# E8-C.net
KiCad netlist of a schematic drawn in EAGLE
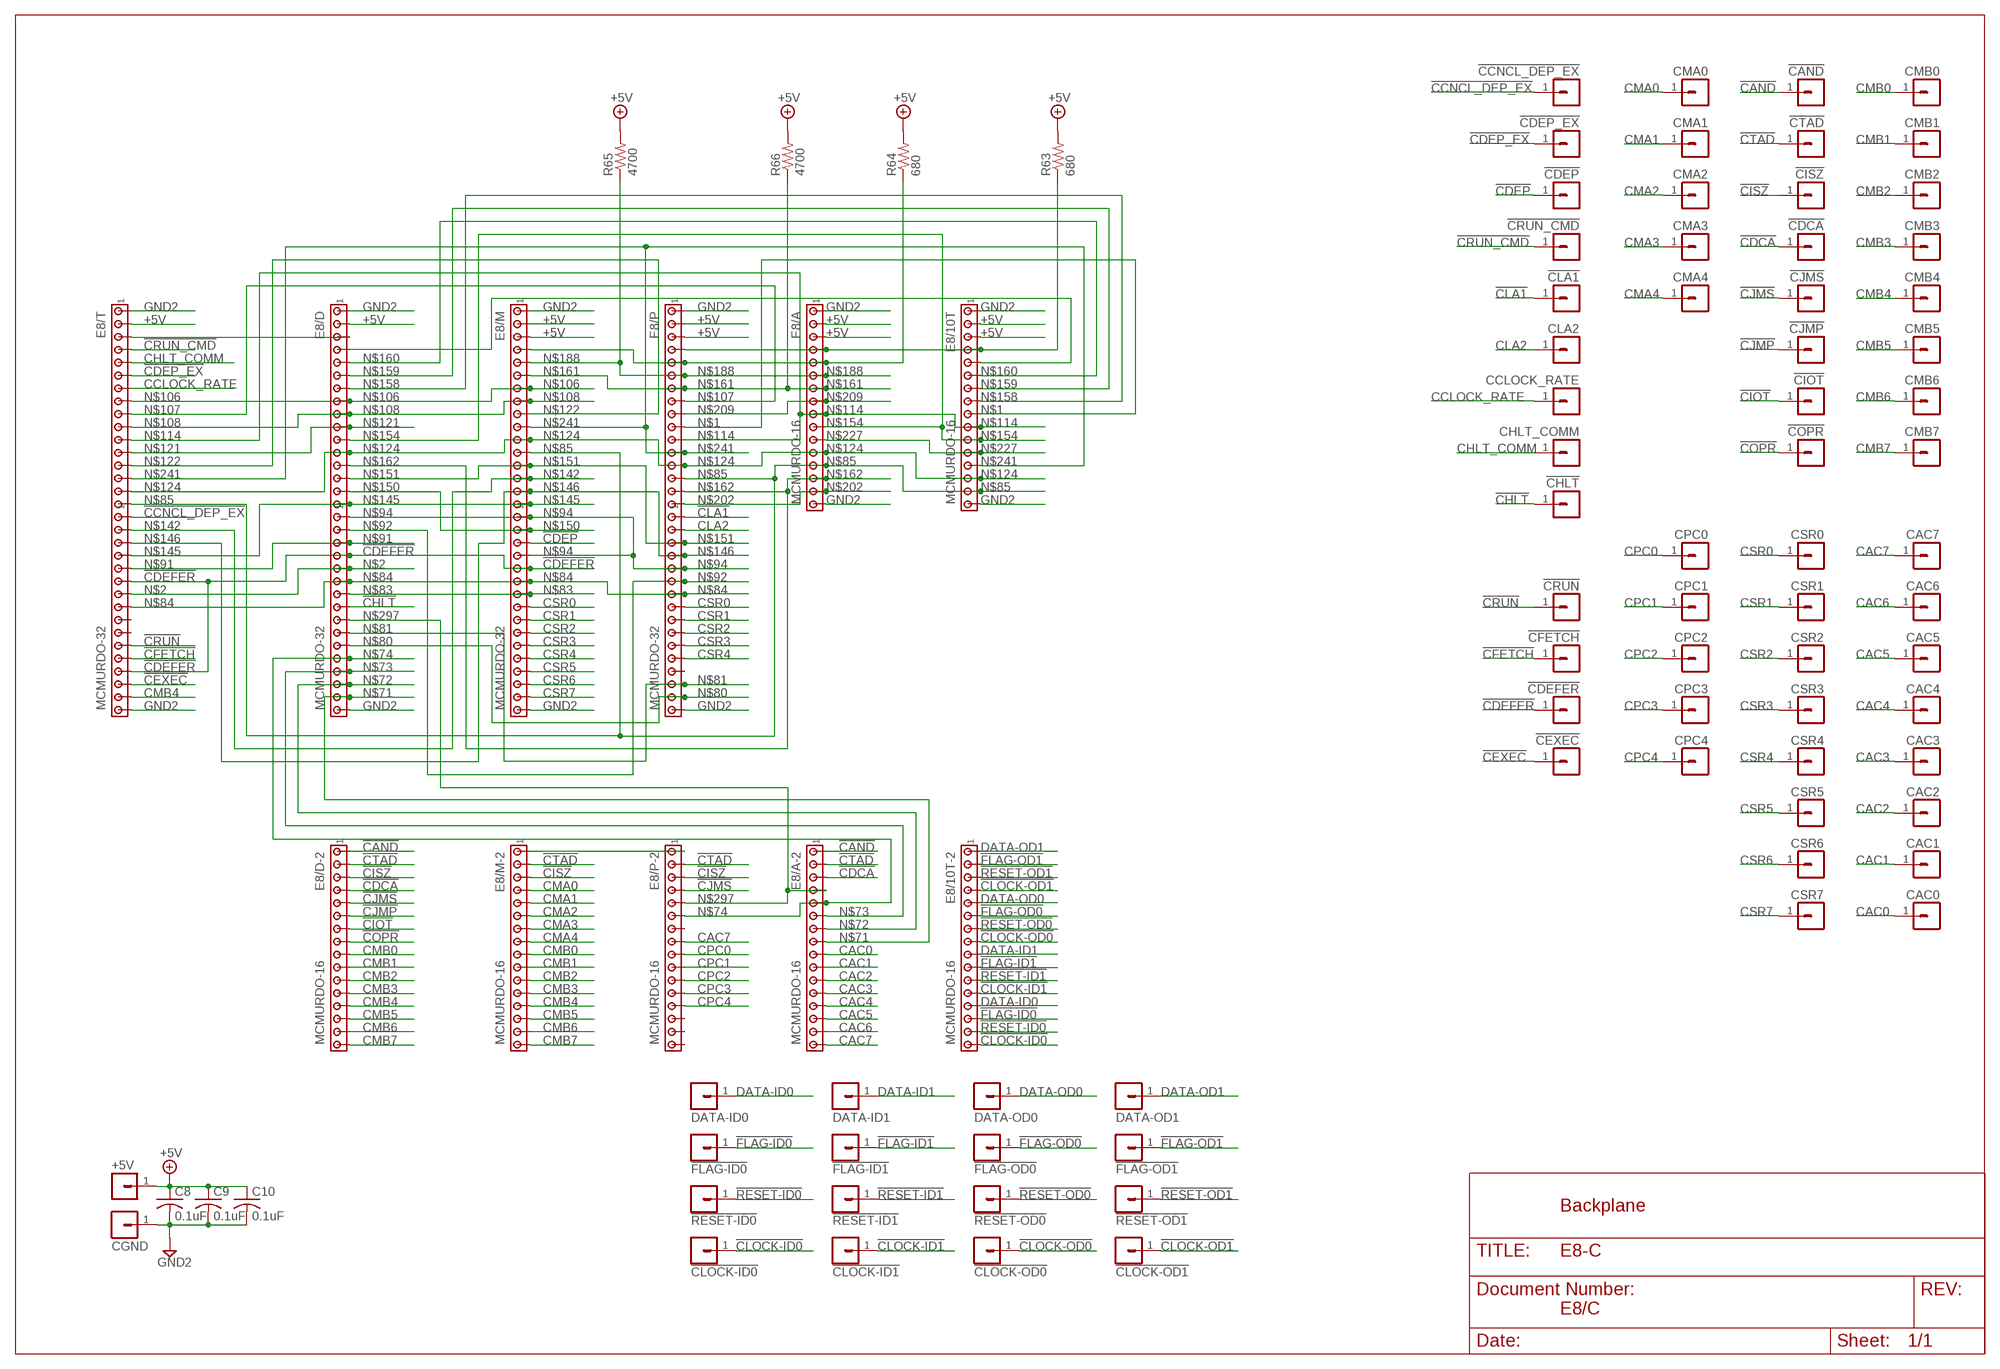
[diagram p0: schematic, sheet 1]

(export (version "E")
  (design (tool "Eeschema 10.0.6"))
  (components
    (comp (ref "!CAND")
      (value "MA01-1")
      (footprint "eagle-import:MA01-1")
      (libsource (lib "eagle-import") (part "MA01-1"))
    )
    (comp (ref "!CCNCL_DEP_EX")
      (value "MA01-1")
      (footprint "eagle-import:MA01-1")
      (libsource (lib "eagle-import") (part "MA01-1"))
    )
    (comp (ref "!CDCA")
      (value "MA01-1")
      (footprint "eagle-import:MA01-1")
      (libsource (lib "eagle-import") (part "MA01-1"))
    )
    (comp (ref "!CDEFER")
      (value "MA01-1")
      (footprint "eagle-import:MA01-1")
      (libsource (lib "eagle-import") (part "MA01-1"))
    )
    (comp (ref "!CDEP")
      (value "MA01-1")
      (footprint "eagle-import:MA01-1")
      (libsource (lib "eagle-import") (part "MA01-1"))
    )
    (comp (ref "!CDEP_EX")
      (value "MA01-1")
      (footprint "eagle-import:MA01-1")
      (libsource (lib "eagle-import") (part "MA01-1"))
    )
    (comp (ref "!CEXEC")
      (value "MA01-1")
      (footprint "eagle-import:MA01-1")
      (libsource (lib "eagle-import") (part "MA01-1"))
    )
    (comp (ref "!CFETCH")
      (value "MA01-1")
      (footprint "eagle-import:MA01-1")
      (libsource (lib "eagle-import") (part "MA01-1"))
    )
    (comp (ref "!CHLT")
      (value "MA01-1")
      (footprint "eagle-import:MA01-1")
      (libsource (lib "eagle-import") (part "MA01-1"))
    )
    (comp (ref "!CIOT")
      (value "MA01-1")
      (footprint "eagle-import:MA01-1")
      (libsource (lib "eagle-import") (part "MA01-1"))
    )
    (comp (ref "!CISZ")
      (value "MA01-1")
      (footprint "eagle-import:MA01-1")
      (libsource (lib "eagle-import") (part "MA01-1"))
    )
    (comp (ref "!CJMP")
      (value "MA01-1")
      (footprint "eagle-import:MA01-1")
      (libsource (lib "eagle-import") (part "MA01-1"))
    )
    (comp (ref "!CJMS")
      (value "MA01-1")
      (footprint "eagle-import:MA01-1")
      (libsource (lib "eagle-import") (part "MA01-1"))
    )
    (comp (ref "!CLA1")
      (value "MA01-1")
      (footprint "eagle-import:MA01-1")
      (libsource (lib "eagle-import") (part "MA01-1"))
    )
    (comp (ref "!CLOCK-ID0")
      (value "MA01-1")
      (footprint "eagle-import:MA01-1")
      (libsource (lib "eagle-import") (part "MA01-1"))
    )
    (comp (ref "!CLOCK-ID1")
      (value "MA01-1")
      (footprint "eagle-import:MA01-1")
      (libsource (lib "eagle-import") (part "MA01-1"))
    )
    (comp (ref "!CLOCK-OD0")
      (value "MA01-1")
      (footprint "eagle-import:MA01-1")
      (libsource (lib "eagle-import") (part "MA01-1"))
    )
    (comp (ref "!CLOCK-OD1")
      (value "MA01-1")
      (footprint "eagle-import:MA01-1")
      (libsource (lib "eagle-import") (part "MA01-1"))
    )
    (comp (ref "!COPR")
      (value "MA01-1")
      (footprint "eagle-import:MA01-1")
      (libsource (lib "eagle-import") (part "MA01-1"))
    )
    (comp (ref "!CRUN")
      (value "MA01-1")
      (footprint "eagle-import:MA01-1")
      (libsource (lib "eagle-import") (part "MA01-1"))
    )
    (comp (ref "!CRUN_CMD")
      (value "MA01-1")
      (footprint "eagle-import:MA01-1")
      (libsource (lib "eagle-import") (part "MA01-1"))
    )
    (comp (ref "!CTAD")
      (value "MA01-1")
      (footprint "eagle-import:MA01-1")
      (libsource (lib "eagle-import") (part "MA01-1"))
    )
    (comp (ref "!FLAG-ID0")
      (value "MA01-1")
      (footprint "eagle-import:MA01-1")
      (libsource (lib "eagle-import") (part "MA01-1"))
    )
    (comp (ref "!FLAG-ID1")
      (value "MA01-1")
      (footprint "eagle-import:MA01-1")
      (libsource (lib "eagle-import") (part "MA01-1"))
    )
    (comp (ref "!FLAG-OD0")
      (value "MA01-1")
      (footprint "eagle-import:MA01-1")
      (libsource (lib "eagle-import") (part "MA01-1"))
    )
    (comp (ref "!FLAG-OD1")
      (value "MA01-1")
      (footprint "eagle-import:MA01-1")
      (libsource (lib "eagle-import") (part "MA01-1"))
    )
    (comp (ref "!RESET-ID0")
      (value "MA01-1")
      (footprint "eagle-import:MA01-1")
      (libsource (lib "eagle-import") (part "MA01-1"))
    )
    (comp (ref "!RESET-ID1")
      (value "MA01-1")
      (footprint "eagle-import:MA01-1")
      (libsource (lib "eagle-import") (part "MA01-1"))
    )
    (comp (ref "!RESET-OD0")
      (value "MA01-1")
      (footprint "eagle-import:MA01-1")
      (libsource (lib "eagle-import") (part "MA01-1"))
    )
    (comp (ref "!RESET-OD1")
      (value "MA01-1")
      (footprint "eagle-import:MA01-1")
      (libsource (lib "eagle-import") (part "MA01-1"))
    )
    (comp (ref "+5V")
      (value "MA01-1")
      (footprint "eagle-import:MA01-1")
      (libsource (lib "eagle-import") (part "MA01-1"))
    )
    (comp (ref "C8")
      (value "0.1uF")
      (footprint "eagle-import:C075-032X103")
      (libsource (lib "eagle-import") (part "C-US075-032X103"))
    )
    (comp (ref "C9")
      (value "0.1uF")
      (footprint "eagle-import:C075-032X103")
      (libsource (lib "eagle-import") (part "C-US075-032X103"))
    )
    (comp (ref "C10")
      (value "0.1uF")
      (footprint "eagle-import:C075-032X103")
      (libsource (lib "eagle-import") (part "C-US075-032X103"))
    )
    (comp (ref "CAC0")
      (value "MA01-1")
      (footprint "eagle-import:MA01-1")
      (libsource (lib "eagle-import") (part "MA01-1"))
    )
    (comp (ref "CAC1")
      (value "MA01-1")
      (footprint "eagle-import:MA01-1")
      (libsource (lib "eagle-import") (part "MA01-1"))
    )
    (comp (ref "CAC2")
      (value "MA01-1")
      (footprint "eagle-import:MA01-1")
      (libsource (lib "eagle-import") (part "MA01-1"))
    )
    (comp (ref "CAC3")
      (value "MA01-1")
      (footprint "eagle-import:MA01-1")
      (libsource (lib "eagle-import") (part "MA01-1"))
    )
    (comp (ref "CAC4")
      (value "MA01-1")
      (footprint "eagle-import:MA01-1")
      (libsource (lib "eagle-import") (part "MA01-1"))
    )
    (comp (ref "CAC5")
      (value "MA01-1")
      (footprint "eagle-import:MA01-1")
      (libsource (lib "eagle-import") (part "MA01-1"))
    )
    (comp (ref "CAC6")
      (value "MA01-1")
      (footprint "eagle-import:MA01-1")
      (libsource (lib "eagle-import") (part "MA01-1"))
    )
    (comp (ref "CAC7")
      (value "MA01-1")
      (footprint "eagle-import:MA01-1")
      (libsource (lib "eagle-import") (part "MA01-1"))
    )
    (comp (ref "CCLOCK_RATE")
      (value "MA01-1")
      (footprint "eagle-import:MA01-1")
      (libsource (lib "eagle-import") (part "MA01-1"))
    )
    (comp (ref "CGND")
      (value "MA01-1")
      (footprint "eagle-import:MA01-1")
      (libsource (lib "eagle-import") (part "MA01-1"))
    )
    (comp (ref "CHLT_COMM")
      (value "MA01-1")
      (footprint "eagle-import:MA01-1")
      (libsource (lib "eagle-import") (part "MA01-1"))
    )
    (comp (ref "CLA2")
      (value "MA01-1")
      (footprint "eagle-import:MA01-1")
      (libsource (lib "eagle-import") (part "MA01-1"))
    )
    (comp (ref "CMA0")
      (value "MA01-1")
      (footprint "eagle-import:MA01-1")
      (libsource (lib "eagle-import") (part "MA01-1"))
    )
    (comp (ref "CMA1")
      (value "MA01-1")
      (footprint "eagle-import:MA01-1")
      (libsource (lib "eagle-import") (part "MA01-1"))
    )
    (comp (ref "CMA2")
      (value "MA01-1")
      (footprint "eagle-import:MA01-1")
      (libsource (lib "eagle-import") (part "MA01-1"))
    )
    (comp (ref "CMA3")
      (value "MA01-1")
      (footprint "eagle-import:MA01-1")
      (libsource (lib "eagle-import") (part "MA01-1"))
    )
    (comp (ref "CMA4")
      (value "MA01-1")
      (footprint "eagle-import:MA01-1")
      (libsource (lib "eagle-import") (part "MA01-1"))
    )
    (comp (ref "CMB0")
      (value "MA01-1")
      (footprint "eagle-import:MA01-1")
      (libsource (lib "eagle-import") (part "MA01-1"))
    )
    (comp (ref "CMB1")
      (value "MA01-1")
      (footprint "eagle-import:MA01-1")
      (libsource (lib "eagle-import") (part "MA01-1"))
    )
    (comp (ref "CMB2")
      (value "MA01-1")
      (footprint "eagle-import:MA01-1")
      (libsource (lib "eagle-import") (part "MA01-1"))
    )
    (comp (ref "CMB3")
      (value "MA01-1")
      (footprint "eagle-import:MA01-1")
      (libsource (lib "eagle-import") (part "MA01-1"))
    )
    (comp (ref "CMB4")
      (value "MA01-1")
      (footprint "eagle-import:MA01-1")
      (libsource (lib "eagle-import") (part "MA01-1"))
    )
    (comp (ref "CMB5")
      (value "MA01-1")
      (footprint "eagle-import:MA01-1")
      (libsource (lib "eagle-import") (part "MA01-1"))
    )
    (comp (ref "CMB6")
      (value "MA01-1")
      (footprint "eagle-import:MA01-1")
      (libsource (lib "eagle-import") (part "MA01-1"))
    )
    (comp (ref "CMB7")
      (value "MA01-1")
      (footprint "eagle-import:MA01-1")
      (libsource (lib "eagle-import") (part "MA01-1"))
    )
    (comp (ref "CPC0")
      (value "MA01-1")
      (footprint "eagle-import:MA01-1")
      (libsource (lib "eagle-import") (part "MA01-1"))
    )
    (comp (ref "CPC1")
      (value "MA01-1")
      (footprint "eagle-import:MA01-1")
      (libsource (lib "eagle-import") (part "MA01-1"))
    )
    (comp (ref "CPC2")
      (value "MA01-1")
      (footprint "eagle-import:MA01-1")
      (libsource (lib "eagle-import") (part "MA01-1"))
    )
    (comp (ref "CPC3")
      (value "MA01-1")
      (footprint "eagle-import:MA01-1")
      (libsource (lib "eagle-import") (part "MA01-1"))
    )
    (comp (ref "CPC4")
      (value "MA01-1")
      (footprint "eagle-import:MA01-1")
      (libsource (lib "eagle-import") (part "MA01-1"))
    )
    (comp (ref "CSR0")
      (value "MA01-1")
      (footprint "eagle-import:MA01-1")
      (libsource (lib "eagle-import") (part "MA01-1"))
    )
    (comp (ref "CSR1")
      (value "MA01-1")
      (footprint "eagle-import:MA01-1")
      (libsource (lib "eagle-import") (part "MA01-1"))
    )
    (comp (ref "CSR2")
      (value "MA01-1")
      (footprint "eagle-import:MA01-1")
      (libsource (lib "eagle-import") (part "MA01-1"))
    )
    (comp (ref "CSR3")
      (value "MA01-1")
      (footprint "eagle-import:MA01-1")
      (libsource (lib "eagle-import") (part "MA01-1"))
    )
    (comp (ref "CSR4")
      (value "MA01-1")
      (footprint "eagle-import:MA01-1")
      (libsource (lib "eagle-import") (part "MA01-1"))
    )
    (comp (ref "CSR5")
      (value "MA01-1")
      (footprint "eagle-import:MA01-1")
      (libsource (lib "eagle-import") (part "MA01-1"))
    )
    (comp (ref "CSR6")
      (value "MA01-1")
      (footprint "eagle-import:MA01-1")
      (libsource (lib "eagle-import") (part "MA01-1"))
    )
    (comp (ref "CSR7")
      (value "MA01-1")
      (footprint "eagle-import:MA01-1")
      (libsource (lib "eagle-import") (part "MA01-1"))
    )
    (comp (ref "DATA-ID0")
      (value "MA01-1")
      (footprint "eagle-import:MA01-1")
      (libsource (lib "eagle-import") (part "MA01-1"))
    )
    (comp (ref "DATA-ID1")
      (value "MA01-1")
      (footprint "eagle-import:MA01-1")
      (libsource (lib "eagle-import") (part "MA01-1"))
    )
    (comp (ref "DATA-OD0")
      (value "MA01-1")
      (footprint "eagle-import:MA01-1")
      (libsource (lib "eagle-import") (part "MA01-1"))
    )
    (comp (ref "DATA-OD1")
      (value "MA01-1")
      (footprint "eagle-import:MA01-1")
      (libsource (lib "eagle-import") (part "MA01-1"))
    )
    (comp (ref "E8/10T")
      (value "MCMURDO-16")
      (footprint "eagle-import:133-12-17")
      (libsource (lib "eagle-import") (part "MCMURDO-16"))
    )
    (comp (ref "E8/10T-2")
      (value "MCMURDO-16")
      (footprint "eagle-import:133-12-17")
      (libsource (lib "eagle-import") (part "MCMURDO-16"))
    )
    (comp (ref "E8/A")
      (value "MCMURDO-16")
      (footprint "eagle-import:133-12-17")
      (libsource (lib "eagle-import") (part "MCMURDO-16"))
    )
    (comp (ref "E8/A-2")
      (value "MCMURDO-16")
      (footprint "eagle-import:133-12-17")
      (libsource (lib "eagle-import") (part "MCMURDO-16"))
    )
    (comp (ref "E8/D")
      (value "MCMURDO-32")
      (footprint "eagle-import:133-14-17")
      (libsource (lib "eagle-import") (part "MCMURDO-32"))
    )
    (comp (ref "E8/D-2")
      (value "MCMURDO-16")
      (footprint "eagle-import:133-12-17")
      (libsource (lib "eagle-import") (part "MCMURDO-16"))
    )
    (comp (ref "E8/M")
      (value "MCMURDO-32")
      (footprint "eagle-import:133-14-17")
      (libsource (lib "eagle-import") (part "MCMURDO-32"))
    )
    (comp (ref "E8/M-2")
      (value "MCMURDO-16")
      (footprint "eagle-import:133-12-17")
      (libsource (lib "eagle-import") (part "MCMURDO-16"))
    )
    (comp (ref "E8/P")
      (value "MCMURDO-32")
      (footprint "eagle-import:133-14-17")
      (libsource (lib "eagle-import") (part "MCMURDO-32"))
    )
    (comp (ref "E8/P-2")
      (value "MCMURDO-16")
      (footprint "eagle-import:133-12-17")
      (libsource (lib "eagle-import") (part "MCMURDO-16"))
    )
    (comp (ref "E8/T")
      (value "MCMURDO-32")
      (footprint "eagle-import:133-14-17")
      (libsource (lib "eagle-import") (part "MCMURDO-32"))
    )
    (comp (ref "R63")
      (value "680")
      (footprint "eagle-import:0207_15")
      (libsource (lib "eagle-import") (part "R-US_0207/15"))
    )
    (comp (ref "R64")
      (value "680")
      (footprint "eagle-import:0207_15")
      (libsource (lib "eagle-import") (part "R-US_0207/15"))
    )
    (comp (ref "R65")
      (value "4700")
      (footprint "eagle-import:0207_15")
      (libsource (lib "eagle-import") (part "R-US_0207/15"))
    )
    (comp (ref "R66")
      (value "4700")
      (footprint "eagle-import:0207_15")
      (libsource (lib "eagle-import") (part "R-US_0207/15"))
    )
  )
  (nets
    (net (code "1") (name "+5V") (class "Default")
      (node (ref "+5V") (pin "1") (pinfunction "1_1") (pintype "passive"))
      (node (ref "C10") (pin "1") (pinfunction "1_1") (pintype "passive"))
      (node (ref "C8") (pin "1") (pinfunction "1_1") (pintype "passive"))
      (node (ref "C9") (pin "1") (pinfunction "1_1") (pintype "passive"))
      (node (ref "E8/10T") (pin "2") (pinfunction "2_2") (pintype "passive"))
      (node (ref "E8/10T") (pin "3") (pinfunction "3_3") (pintype "passive"))
      (node (ref "E8/A") (pin "2") (pinfunction "2_2") (pintype "passive"))
      (node (ref "E8/A") (pin "3") (pinfunction "3_3") (pintype "passive"))
      (node (ref "E8/D") (pin "2") (pinfunction "2_2") (pintype "passive"))
      (node (ref "E8/M") (pin "2") (pinfunction "2_2") (pintype "passive"))
      (node (ref "E8/M") (pin "3") (pinfunction "3_3") (pintype "passive"))
      (node (ref "E8/P") (pin "2") (pinfunction "2_2") (pintype "passive"))
      (node (ref "E8/P") (pin "3") (pinfunction "3_3") (pintype "passive"))
      (node (ref "E8/T") (pin "2") (pinfunction "2_2") (pintype "passive"))
      (node (ref "R63") (pin "2") (pinfunction "2_2") (pintype "passive"))
      (node (ref "R64") (pin "2") (pinfunction "2_2") (pintype "passive"))
      (node (ref "R65") (pin "2") (pinfunction "2_2") (pintype "passive"))
      (node (ref "R66") (pin "2") (pinfunction "2_2") (pintype "passive"))
    )
    (net (code "2") (name "/CAC0") (class "Default")
      (node (ref "CAC0") (pin "1") (pinfunction "1_1") (pintype "passive"))
      (node (ref "E8/A-2") (pin "9") (pinfunction "9_9") (pintype "passive"))
    )
    (net (code "3") (name "/CAC1") (class "Default")
      (node (ref "CAC1") (pin "1") (pinfunction "1_1") (pintype "passive"))
      (node (ref "E8/A-2") (pin "10") (pinfunction "10_10") (pintype "passive"))
    )
    (net (code "4") (name "/CAC2") (class "Default")
      (node (ref "CAC2") (pin "1") (pinfunction "1_1") (pintype "passive"))
      (node (ref "E8/A-2") (pin "11") (pinfunction "11_11") (pintype "passive"))
    )
    (net (code "5") (name "/CAC3") (class "Default")
      (node (ref "CAC3") (pin "1") (pinfunction "1_1") (pintype "passive"))
      (node (ref "E8/A-2") (pin "12") (pinfunction "12_12") (pintype "passive"))
    )
    (net (code "6") (name "/CAC4") (class "Default")
      (node (ref "CAC4") (pin "1") (pinfunction "1_1") (pintype "passive"))
      (node (ref "E8/A-2") (pin "13") (pinfunction "13_13") (pintype "passive"))
    )
    (net (code "7") (name "/CAC5") (class "Default")
      (node (ref "CAC5") (pin "1") (pinfunction "1_1") (pintype "passive"))
      (node (ref "E8/A-2") (pin "14") (pinfunction "14_14") (pintype "passive"))
    )
    (net (code "8") (name "/CAC6") (class "Default")
      (node (ref "CAC6") (pin "1") (pinfunction "1_1") (pintype "passive"))
      (node (ref "E8/A-2") (pin "15") (pinfunction "15_15") (pintype "passive"))
    )
    (net (code "9") (name "/CAC7") (class "Default")
      (node (ref "CAC7") (pin "1") (pinfunction "1_1") (pintype "passive"))
      (node (ref "E8/A-2") (pin "16") (pinfunction "16_16") (pintype "passive"))
      (node (ref "E8/P-2") (pin "8") (pinfunction "8_8") (pintype "passive"))
    )
    (net (code "10") (name "/CCLOCK_RATE") (class "Default")
      (node (ref "CCLOCK_RATE") (pin "1") (pinfunction "1_1") (pintype "passive"))
      (node (ref "E8/T") (pin "7") (pinfunction "7_7") (pintype "passive"))
    )
    (net (code "11") (name "/CHLT_COMM") (class "Default")
      (node (ref "CHLT_COMM") (pin "1") (pinfunction "1_1") (pintype "passive"))
      (node (ref "E8/T") (pin "5") (pinfunction "5_5") (pintype "passive"))
    )
    (net (code "12") (name "/CLA2") (class "Default")
      (node (ref "CLA2") (pin "1") (pinfunction "1_1") (pintype "passive"))
      (node (ref "E8/P") (pin "18") (pinfunction "18_18") (pintype "passive"))
    )
    (net (code "13") (name "/CMA0") (class "Default")
      (node (ref "CMA0") (pin "1") (pinfunction "1_1") (pintype "passive"))
      (node (ref "E8/M-2") (pin "4") (pinfunction "4_4") (pintype "passive"))
    )
    (net (code "14") (name "/CMA1") (class "Default")
      (node (ref "CMA1") (pin "1") (pinfunction "1_1") (pintype "passive"))
      (node (ref "E8/M-2") (pin "5") (pinfunction "5_5") (pintype "passive"))
    )
    (net (code "15") (name "/CMA2") (class "Default")
      (node (ref "CMA2") (pin "1") (pinfunction "1_1") (pintype "passive"))
      (node (ref "E8/M-2") (pin "6") (pinfunction "6_6") (pintype "passive"))
    )
    (net (code "16") (name "/CMA3") (class "Default")
      (node (ref "CMA3") (pin "1") (pinfunction "1_1") (pintype "passive"))
      (node (ref "E8/M-2") (pin "7") (pinfunction "7_7") (pintype "passive"))
    )
    (net (code "17") (name "/CMA4") (class "Default")
      (node (ref "CMA4") (pin "1") (pinfunction "1_1") (pintype "passive"))
      (node (ref "E8/M-2") (pin "8") (pinfunction "8_8") (pintype "passive"))
    )
    (net (code "18") (name "/CMB0") (class "Default")
      (node (ref "CMB0") (pin "1") (pinfunction "1_1") (pintype "passive"))
      (node (ref "E8/D-2") (pin "9") (pinfunction "9_9") (pintype "passive"))
      (node (ref "E8/M-2") (pin "9") (pinfunction "9_9") (pintype "passive"))
    )
    (net (code "19") (name "/CMB1") (class "Default")
      (node (ref "CMB1") (pin "1") (pinfunction "1_1") (pintype "passive"))
      (node (ref "E8/D-2") (pin "10") (pinfunction "10_10") (pintype "passive"))
      (node (ref "E8/M-2") (pin "10") (pinfunction "10_10") (pintype "passive"))
    )
    (net (code "20") (name "/CMB2") (class "Default")
      (node (ref "CMB2") (pin "1") (pinfunction "1_1") (pintype "passive"))
      (node (ref "E8/D-2") (pin "11") (pinfunction "11_11") (pintype "passive"))
      (node (ref "E8/M-2") (pin "11") (pinfunction "11_11") (pintype "passive"))
    )
    (net (code "21") (name "/CMB3") (class "Default")
      (node (ref "CMB3") (pin "1") (pinfunction "1_1") (pintype "passive"))
      (node (ref "E8/D-2") (pin "12") (pinfunction "12_12") (pintype "passive"))
      (node (ref "E8/M-2") (pin "12") (pinfunction "12_12") (pintype "passive"))
    )
    (net (code "22") (name "/CMB4") (class "Default")
      (node (ref "CMB4") (pin "1") (pinfunction "1_1") (pintype "passive"))
      (node (ref "E8/D-2") (pin "13") (pinfunction "13_13") (pintype "passive"))
      (node (ref "E8/M-2") (pin "13") (pinfunction "13_13") (pintype "passive"))
      (node (ref "E8/T") (pin "31") (pinfunction "31_31") (pintype "passive"))
    )
    (net (code "23") (name "/CMB5") (class "Default")
      (node (ref "CMB5") (pin "1") (pinfunction "1_1") (pintype "passive"))
      (node (ref "E8/D-2") (pin "14") (pinfunction "14_14") (pintype "passive"))
      (node (ref "E8/M-2") (pin "14") (pinfunction "14_14") (pintype "passive"))
    )
    (net (code "24") (name "/CMB6") (class "Default")
      (node (ref "CMB6") (pin "1") (pinfunction "1_1") (pintype "passive"))
      (node (ref "E8/D-2") (pin "15") (pinfunction "15_15") (pintype "passive"))
      (node (ref "E8/M-2") (pin "15") (pinfunction "15_15") (pintype "passive"))
    )
    (net (code "25") (name "/CMB7") (class "Default")
      (node (ref "CMB7") (pin "1") (pinfunction "1_1") (pintype "passive"))
      (node (ref "E8/D-2") (pin "16") (pinfunction "16_16") (pintype "passive"))
      (node (ref "E8/M-2") (pin "16") (pinfunction "16_16") (pintype "passive"))
    )
    (net (code "26") (name "/CPC0") (class "Default")
      (node (ref "CPC0") (pin "1") (pinfunction "1_1") (pintype "passive"))
      (node (ref "E8/P-2") (pin "9") (pinfunction "9_9") (pintype "passive"))
    )
    (net (code "27") (name "/CPC1") (class "Default")
      (node (ref "CPC1") (pin "1") (pinfunction "1_1") (pintype "passive"))
      (node (ref "E8/P-2") (pin "10") (pinfunction "10_10") (pintype "passive"))
    )
    (net (code "28") (name "/CPC2") (class "Default")
      (node (ref "CPC2") (pin "1") (pinfunction "1_1") (pintype "passive"))
      (node (ref "E8/P-2") (pin "11") (pinfunction "11_11") (pintype "passive"))
    )
    (net (code "29") (name "/CPC3") (class "Default")
      (node (ref "CPC3") (pin "1") (pinfunction "1_1") (pintype "passive"))
      (node (ref "E8/P-2") (pin "12") (pinfunction "12_12") (pintype "passive"))
    )
    (net (code "30") (name "/CPC4") (class "Default")
      (node (ref "CPC4") (pin "1") (pinfunction "1_1") (pintype "passive"))
      (node (ref "E8/P-2") (pin "13") (pinfunction "13_13") (pintype "passive"))
    )
    (net (code "31") (name "/CSR0") (class "Default")
      (node (ref "CSR0") (pin "1") (pinfunction "1_1") (pintype "passive"))
      (node (ref "E8/M") (pin "24") (pinfunction "24_24") (pintype "passive"))
      (node (ref "E8/P") (pin "24") (pinfunction "24_24") (pintype "passive"))
    )
    (net (code "32") (name "/CSR1") (class "Default")
      (node (ref "CSR1") (pin "1") (pinfunction "1_1") (pintype "passive"))
      (node (ref "E8/M") (pin "25") (pinfunction "25_25") (pintype "passive"))
      (node (ref "E8/P") (pin "25") (pinfunction "25_25") (pintype "passive"))
    )
    (net (code "33") (name "/CSR2") (class "Default")
      (node (ref "CSR2") (pin "1") (pinfunction "1_1") (pintype "passive"))
      (node (ref "E8/M") (pin "26") (pinfunction "26_26") (pintype "passive"))
      (node (ref "E8/P") (pin "26") (pinfunction "26_26") (pintype "passive"))
    )
    (net (code "34") (name "/CSR3") (class "Default")
      (node (ref "CSR3") (pin "1") (pinfunction "1_1") (pintype "passive"))
      (node (ref "E8/M") (pin "27") (pinfunction "27_27") (pintype "passive"))
      (node (ref "E8/P") (pin "27") (pinfunction "27_27") (pintype "passive"))
    )
    (net (code "35") (name "/CSR4") (class "Default")
      (node (ref "CSR4") (pin "1") (pinfunction "1_1") (pintype "passive"))
      (node (ref "E8/M") (pin "28") (pinfunction "28_28") (pintype "passive"))
      (node (ref "E8/P") (pin "28") (pinfunction "28_28") (pintype "passive"))
    )
    (net (code "36") (name "/CSR5") (class "Default")
      (node (ref "CSR5") (pin "1") (pinfunction "1_1") (pintype "passive"))
      (node (ref "E8/M") (pin "29") (pinfunction "29_29") (pintype "passive"))
    )
    (net (code "37") (name "/CSR6") (class "Default")
      (node (ref "CSR6") (pin "1") (pinfunction "1_1") (pintype "passive"))
      (node (ref "E8/M") (pin "30") (pinfunction "30_30") (pintype "passive"))
    )
    (net (code "38") (name "/CSR7") (class "Default")
      (node (ref "CSR7") (pin "1") (pinfunction "1_1") (pintype "passive"))
      (node (ref "E8/M") (pin "31") (pinfunction "31_31") (pintype "passive"))
    )
    (net (code "39") (name "/DATA-ID0") (class "Default")
      (node (ref "DATA-ID0") (pin "1") (pinfunction "1_1") (pintype "passive"))
      (node (ref "E8/10T-2") (pin "13") (pinfunction "13_13") (pintype "passive"))
    )
    (net (code "40") (name "/DATA-ID1") (class "Default")
      (node (ref "DATA-ID1") (pin "1") (pinfunction "1_1") (pintype "passive"))
      (node (ref "E8/10T-2") (pin "9") (pinfunction "9_9") (pintype "passive"))
    )
    (net (code "41") (name "/DATA-OD0") (class "Default")
      (node (ref "DATA-OD0") (pin "1") (pinfunction "1_1") (pintype "passive"))
      (node (ref "E8/10T-2") (pin "5") (pinfunction "5_5") (pintype "passive"))
    )
    (net (code "42") (name "/DATA-OD1") (class "Default")
      (node (ref "DATA-OD1") (pin "1") (pinfunction "1_1") (pintype "passive"))
      (node (ref "E8/10T-2") (pin "1") (pinfunction "1_1") (pintype "passive"))
    )
    (net (code "43") (name "/N$1") (class "Default")
      (node (ref "E8/10T") (pin "9") (pinfunction "9_9") (pintype "passive"))
      (node (ref "E8/P") (pin "10") (pinfunction "10_10") (pintype "passive"))
    )
    (net (code "44") (name "/N$2") (class "Default")
      (node (ref "E8/D") (pin "21") (pinfunction "21_21") (pintype "passive"))
      (node (ref "E8/T") (pin "23") (pinfunction "23_23") (pintype "passive"))
    )
    (net (code "45") (name "/N$71") (class "Default")
      (node (ref "E8/A-2") (pin "8") (pinfunction "8_8") (pintype "passive"))
      (node (ref "E8/D") (pin "31") (pinfunction "31_31") (pintype "passive"))
    )
    (net (code "46") (name "/N$72") (class "Default")
      (node (ref "E8/A-2") (pin "7") (pinfunction "7_7") (pintype "passive"))
      (node (ref "E8/D") (pin "30") (pinfunction "30_30") (pintype "passive"))
    )
    (net (code "47") (name "/N$73") (class "Default")
      (node (ref "E8/A-2") (pin "6") (pinfunction "6_6") (pintype "passive"))
      (node (ref "E8/D") (pin "29") (pinfunction "29_29") (pintype "passive"))
    )
    (net (code "48") (name "/N$74") (class "Default")
      (node (ref "E8/A-2") (pin "5") (pinfunction "5_5") (pintype "passive"))
      (node (ref "E8/D") (pin "28") (pinfunction "28_28") (pintype "passive"))
      (node (ref "E8/P-2") (pin "6") (pinfunction "6_6") (pintype "passive"))
    )
    (net (code "49") (name "/N$80") (class "Default")
      (node (ref "E8/D") (pin "27") (pinfunction "27_27") (pintype "passive"))
      (node (ref "E8/P") (pin "31") (pinfunction "31_31") (pintype "passive"))
    )
    (net (code "50") (name "/N$81") (class "Default")
      (node (ref "E8/D") (pin "26") (pinfunction "26_26") (pintype "passive"))
      (node (ref "E8/P") (pin "30") (pinfunction "30_30") (pintype "passive"))
    )
    (net (code "51") (name "/N$83") (class "Default")
      (node (ref "E8/D") (pin "23") (pinfunction "23_23") (pintype "passive"))
      (node (ref "E8/M") (pin "23") (pinfunction "23_23") (pintype "passive"))
    )
    (net (code "52") (name "/N$84") (class "Default")
      (node (ref "E8/D") (pin "22") (pinfunction "22_22") (pintype "passive"))
      (node (ref "E8/M") (pin "22") (pinfunction "22_22") (pintype "passive"))
      (node (ref "E8/P") (pin "23") (pinfunction "23_23") (pintype "passive"))
      (node (ref "E8/T") (pin "24") (pinfunction "24_24") (pintype "passive"))
    )
    (net (code "53") (name "/N$85") (class "Default")
      (node (ref "E8/10T") (pin "15") (pinfunction "15_15") (pintype "passive"))
      (node (ref "E8/A") (pin "13") (pinfunction "13_13") (pintype "passive"))
      (node (ref "E8/M") (pin "12") (pinfunction "12_12") (pintype "passive"))
      (node (ref "E8/P") (pin "14") (pinfunction "14_14") (pintype "passive"))
      (node (ref "E8/T") (pin "16") (pinfunction "16_16") (pintype "passive"))
    )
    (net (code "54") (name "/N$91") (class "Default")
      (node (ref "E8/D") (pin "19") (pinfunction "19_19") (pintype "passive"))
      (node (ref "E8/T") (pin "21") (pinfunction "21_21") (pintype "passive"))
    )
    (net (code "55") (name "/N$92") (class "Default")
      (node (ref "E8/D") (pin "18") (pinfunction "18_18") (pintype "passive"))
      (node (ref "E8/P") (pin "22") (pinfunction "22_22") (pintype "passive"))
    )
    (net (code "56") (name "/N$94") (class "Default")
      (node (ref "E8/D") (pin "17") (pinfunction "17_17") (pintype "passive"))
      (node (ref "E8/M") (pin "17") (pinfunction "17_17") (pintype "passive"))
      (node (ref "E8/M") (pin "20") (pinfunction "20_20") (pintype "passive"))
      (node (ref "E8/P") (pin "21") (pinfunction "21_21") (pintype "passive"))
    )
    (net (code "57") (name "/N$106") (class "Default")
      (node (ref "E8/D") (pin "8") (pinfunction "8_8") (pintype "passive"))
      (node (ref "E8/M") (pin "7") (pinfunction "7_7") (pintype "passive"))
      (node (ref "E8/T") (pin "8") (pinfunction "8_8") (pintype "passive"))
    )
    (net (code "58") (name "/N$107") (class "Default")
      (node (ref "E8/P") (pin "8") (pinfunction "8_8") (pintype "passive"))
      (node (ref "E8/T") (pin "9") (pinfunction "9_9") (pintype "passive"))
    )
    (net (code "59") (name "/N$108") (class "Default")
      (node (ref "E8/D") (pin "9") (pinfunction "9_9") (pintype "passive"))
      (node (ref "E8/M") (pin "8") (pinfunction "8_8") (pintype "passive"))
      (node (ref "E8/T") (pin "10") (pinfunction "10_10") (pintype "passive"))
    )
    (net (code "60") (name "/N$114") (class "Default")
      (node (ref "E8/10T") (pin "10") (pinfunction "10_10") (pintype "passive"))
      (node (ref "E8/A") (pin "9") (pinfunction "9_9") (pintype "passive"))
      (node (ref "E8/P") (pin "11") (pinfunction "11_11") (pintype "passive"))
      (node (ref "E8/T") (pin "11") (pinfunction "11_11") (pintype "passive"))
    )
    (net (code "61") (name "/N$121") (class "Default")
      (node (ref "E8/D") (pin "10") (pinfunction "10_10") (pintype "passive"))
      (node (ref "E8/T") (pin "12") (pinfunction "12_12") (pintype "passive"))
    )
    (net (code "62") (name "/N$122") (class "Default")
      (node (ref "E8/M") (pin "9") (pinfunction "9_9") (pintype "passive"))
      (node (ref "E8/T") (pin "13") (pinfunction "13_13") (pintype "passive"))
    )
    (net (code "63") (name "/N$124") (class "Default")
      (node (ref "E8/10T") (pin "14") (pinfunction "14_14") (pintype "passive"))
      (node (ref "E8/A") (pin "12") (pinfunction "12_12") (pintype "passive"))
      (node (ref "E8/D") (pin "12") (pinfunction "12_12") (pintype "passive"))
      (node (ref "E8/M") (pin "11") (pinfunction "11_11") (pintype "passive"))
      (node (ref "E8/P") (pin "13") (pinfunction "13_13") (pintype "passive"))
      (node (ref "E8/T") (pin "15") (pinfunction "15_15") (pintype "passive"))
    )
    (net (code "64") (name "/N$142") (class "Default")
      (node (ref "E8/M") (pin "14") (pinfunction "14_14") (pintype "passive"))
      (node (ref "E8/T") (pin "18") (pinfunction "18_18") (pintype "passive"))
    )
    (net (code "65") (name "/N$145") (class "Default")
      (node (ref "E8/D") (pin "16") (pinfunction "16_16") (pintype "passive"))
      (node (ref "E8/M") (pin "16") (pinfunction "16_16") (pintype "passive"))
      (node (ref "E8/T") (pin "20") (pinfunction "20_20") (pintype "passive"))
    )
    (net (code "66") (name "/N$146") (class "Default")
      (node (ref "E8/M") (pin "15") (pinfunction "15_15") (pintype "passive"))
      (node (ref "E8/P") (pin "20") (pinfunction "20_20") (pintype "passive"))
      (node (ref "E8/T") (pin "19") (pinfunction "19_19") (pintype "passive"))
    )
    (net (code "67") (name "/N$150") (class "Default")
      (node (ref "E8/D") (pin "15") (pinfunction "15_15") (pintype "passive"))
      (node (ref "E8/M") (pin "18") (pinfunction "18_18") (pintype "passive"))
    )
    (net (code "68") (name "/N$151") (class "Default")
      (node (ref "E8/D") (pin "14") (pinfunction "14_14") (pintype "passive"))
      (node (ref "E8/M") (pin "13") (pinfunction "13_13") (pintype "passive"))
      (node (ref "E8/P") (pin "19") (pinfunction "19_19") (pintype "passive"))
    )
    (net (code "69") (name "/N$154") (class "Default")
      (node (ref "E8/10T") (pin "11") (pinfunction "11_11") (pintype "passive"))
      (node (ref "E8/A") (pin "10") (pinfunction "10_10") (pintype "passive"))
      (node (ref "E8/D") (pin "11") (pinfunction "11_11") (pintype "passive"))
    )
    (net (code "70") (name "/N$158") (class "Default")
      (node (ref "E8/10T") (pin "8") (pinfunction "8_8") (pintype "passive"))
      (node (ref "E8/D") (pin "7") (pinfunction "7_7") (pintype "passive"))
    )
    (net (code "71") (name "/N$159") (class "Default")
      (node (ref "E8/10T") (pin "7") (pinfunction "7_7") (pintype "passive"))
      (node (ref "E8/D") (pin "6") (pinfunction "6_6") (pintype "passive"))
    )
    (net (code "72") (name "/N$160") (class "Default")
      (node (ref "E8/10T") (pin "6") (pinfunction "6_6") (pintype "passive"))
      (node (ref "E8/D") (pin "5") (pinfunction "5_5") (pintype "passive"))
    )
    (net (code "73") (name "/N$161") (class "Default")
      (node (ref "E8/A") (pin "7") (pinfunction "7_7") (pintype "passive"))
      (node (ref "E8/M") (pin "6") (pinfunction "6_6") (pintype "passive"))
      (node (ref "E8/P") (pin "7") (pinfunction "7_7") (pintype "passive"))
      (node (ref "R66") (pin "1") (pinfunction "1_1") (pintype "passive"))
    )
    (net (code "74") (name "/N$162") (class "Default")
      (node (ref "E8/A") (pin "14") (pinfunction "14_14") (pintype "passive"))
      (node (ref "E8/D") (pin "13") (pinfunction "13_13") (pintype "passive"))
      (node (ref "E8/P") (pin "15") (pinfunction "15_15") (pintype "passive"))
    )
    (net (code "75") (name "/N$188") (class "Default")
      (node (ref "E8/A") (pin "6") (pinfunction "6_6") (pintype "passive"))
      (node (ref "E8/M") (pin "5") (pinfunction "5_5") (pintype "passive"))
      (node (ref "E8/P") (pin "6") (pinfunction "6_6") (pintype "passive"))
      (node (ref "R65") (pin "1") (pinfunction "1_1") (pintype "passive"))
    )
    (net (code "76") (name "/N$202") (class "Default")
      (node (ref "E8/A") (pin "15") (pinfunction "15_15") (pintype "passive"))
      (node (ref "E8/P") (pin "16") (pinfunction "16_16") (pintype "passive"))
    )
    (net (code "77") (name "/N$209") (class "Default")
      (node (ref "E8/A") (pin "8") (pinfunction "8_8") (pintype "passive"))
      (node (ref "E8/P") (pin "9") (pinfunction "9_9") (pintype "passive"))
    )
    (net (code "78") (name "/N$227") (class "Default")
      (node (ref "E8/10T") (pin "12") (pinfunction "12_12") (pintype "passive"))
      (node (ref "E8/A") (pin "11") (pinfunction "11_11") (pintype "passive"))
    )
    (net (code "79") (name "/N$241") (class "Default")
      (node (ref "E8/10T") (pin "13") (pinfunction "13_13") (pintype "passive"))
      (node (ref "E8/M") (pin "10") (pinfunction "10_10") (pintype "passive"))
      (node (ref "E8/P") (pin "12") (pinfunction "12_12") (pintype "passive"))
      (node (ref "E8/T") (pin "14") (pinfunction "14_14") (pintype "passive"))
    )
    (net (code "80") (name "/N$297") (class "Default")
      (node (ref "E8/A-2") (pin "4") (pinfunction "4_4") (pintype "passive"))
      (node (ref "E8/D") (pin "25") (pinfunction "25_25") (pintype "passive"))
      (node (ref "E8/P-2") (pin "5") (pinfunction "5_5") (pintype "passive"))
    )
    (net (code "81") (name "/~{CAND}") (class "Default")
      (node (ref "!CAND") (pin "1") (pinfunction "1_1") (pintype "passive"))
      (node (ref "E8/A-2") (pin "1") (pinfunction "1_1") (pintype "passive"))
      (node (ref "E8/D-2") (pin "1") (pinfunction "1_1") (pintype "passive"))
    )
    (net (code "82") (name "/~{CCNCL_DEP_EX}") (class "Default")
      (node (ref "!CCNCL_DEP_EX") (pin "1") (pinfunction "1_1") (pintype "passive"))
      (node (ref "E8/T") (pin "17") (pinfunction "17_17") (pintype "passive"))
    )
    (net (code "83") (name "/~{CDCA}") (class "Default")
      (node (ref "!CDCA") (pin "1") (pinfunction "1_1") (pintype "passive"))
      (node (ref "E8/A-2") (pin "3") (pinfunction "3_3") (pintype "passive"))
      (node (ref "E8/D-2") (pin "4") (pinfunction "4_4") (pintype "passive"))
    )
    (net (code "84") (name "/~{CDEFER}") (class "Default")
      (node (ref "!CDEFER") (pin "1") (pinfunction "1_1") (pintype "passive"))
      (node (ref "E8/D") (pin "20") (pinfunction "20_20") (pintype "passive"))
      (node (ref "E8/M") (pin "21") (pinfunction "21_21") (pintype "passive"))
      (node (ref "E8/T") (pin "22") (pinfunction "22_22") (pintype "passive"))
      (node (ref "E8/T") (pin "29") (pinfunction "29_29") (pintype "passive"))
    )
    (net (code "85") (name "/~{CDEP_EX}") (class "Default")
      (node (ref "!CDEP_EX") (pin "1") (pinfunction "1_1") (pintype "passive"))
      (node (ref "E8/T") (pin "6") (pinfunction "6_6") (pintype "passive"))
    )
    (net (code "86") (name "/~{CDEP}") (class "Default")
      (node (ref "!CDEP") (pin "1") (pinfunction "1_1") (pintype "passive"))
      (node (ref "E8/M") (pin "19") (pinfunction "19_19") (pintype "passive"))
    )
    (net (code "87") (name "/~{CEXEC}") (class "Default")
      (node (ref "!CEXEC") (pin "1") (pinfunction "1_1") (pintype "passive"))
      (node (ref "E8/T") (pin "30") (pinfunction "30_30") (pintype "passive"))
    )
    (net (code "88") (name "/~{CFETCH}") (class "Default")
      (node (ref "!CFETCH") (pin "1") (pinfunction "1_1") (pintype "passive"))
      (node (ref "E8/T") (pin "28") (pinfunction "28_28") (pintype "passive"))
    )
    (net (code "89") (name "/~{CHLT}") (class "Default")
      (node (ref "!CHLT") (pin "1") (pinfunction "1_1") (pintype "passive"))
      (node (ref "E8/D") (pin "24") (pinfunction "24_24") (pintype "passive"))
    )
    (net (code "90") (name "/~{CIOT}") (class "Default")
      (node (ref "!CIOT") (pin "1") (pinfunction "1_1") (pintype "passive"))
      (node (ref "E8/D-2") (pin "7") (pinfunction "7_7") (pintype "passive"))
    )
    (net (code "91") (name "/~{CISZ}") (class "Default")
      (node (ref "!CISZ") (pin "1") (pinfunction "1_1") (pintype "passive"))
      (node (ref "E8/D-2") (pin "3") (pinfunction "3_3") (pintype "passive"))
      (node (ref "E8/M-2") (pin "3") (pinfunction "3_3") (pintype "passive"))
      (node (ref "E8/P-2") (pin "3") (pinfunction "3_3") (pintype "passive"))
    )
    (net (code "92") (name "/~{CJMP}") (class "Default")
      (node (ref "!CJMP") (pin "1") (pinfunction "1_1") (pintype "passive"))
      (node (ref "E8/D-2") (pin "6") (pinfunction "6_6") (pintype "passive"))
    )
    (net (code "93") (name "/~{CJMS}") (class "Default")
      (node (ref "!CJMS") (pin "1") (pinfunction "1_1") (pintype "passive"))
      (node (ref "E8/D-2") (pin "5") (pinfunction "5_5") (pintype "passive"))
      (node (ref "E8/P-2") (pin "4") (pinfunction "4_4") (pintype "passive"))
    )
    (net (code "94") (name "/~{CLA1}") (class "Default")
      (node (ref "!CLA1") (pin "1") (pinfunction "1_1") (pintype "passive"))
      (node (ref "E8/P") (pin "17") (pinfunction "17_17") (pintype "passive"))
    )
    (net (code "95") (name "/~{CLOCK-ID0}") (class "Default")
      (node (ref "!CLOCK-ID0") (pin "1") (pinfunction "1_1") (pintype "passive"))
      (node (ref "E8/10T-2") (pin "16") (pinfunction "16_16") (pintype "passive"))
    )
    (net (code "96") (name "/~{CLOCK-ID1}") (class "Default")
      (node (ref "!CLOCK-ID1") (pin "1") (pinfunction "1_1") (pintype "passive"))
      (node (ref "E8/10T-2") (pin "12") (pinfunction "12_12") (pintype "passive"))
    )
    (net (code "97") (name "/~{CLOCK-OD0}") (class "Default")
      (node (ref "!CLOCK-OD0") (pin "1") (pinfunction "1_1") (pintype "passive"))
      (node (ref "E8/10T-2") (pin "8") (pinfunction "8_8") (pintype "passive"))
    )
    (net (code "98") (name "/~{CLOCK-OD1}") (class "Default")
      (node (ref "!CLOCK-OD1") (pin "1") (pinfunction "1_1") (pintype "passive"))
      (node (ref "E8/10T-2") (pin "4") (pinfunction "4_4") (pintype "passive"))
    )
    (net (code "99") (name "/~{COPR}") (class "Default")
      (node (ref "!COPR") (pin "1") (pinfunction "1_1") (pintype "passive"))
      (node (ref "E8/D-2") (pin "8") (pinfunction "8_8") (pintype "passive"))
    )
    (net (code "100") (name "/~{CRUN_CMD}") (class "Default")
      (node (ref "!CRUN_CMD") (pin "1") (pinfunction "1_1") (pintype "passive"))
      (node (ref "E8/T") (pin "4") (pinfunction "4_4") (pintype "passive"))
    )
    (net (code "101") (name "/~{CRUN}") (class "Default")
      (node (ref "!CRUN") (pin "1") (pinfunction "1_1") (pintype "passive"))
      (node (ref "E8/T") (pin "27") (pinfunction "27_27") (pintype "passive"))
    )
    (net (code "102") (name "/~{CTAD}") (class "Default")
      (node (ref "!CTAD") (pin "1") (pinfunction "1_1") (pintype "passive"))
      (node (ref "E8/A-2") (pin "2") (pinfunction "2_2") (pintype "passive"))
      (node (ref "E8/D-2") (pin "2") (pinfunction "2_2") (pintype "passive"))
      (node (ref "E8/M-2") (pin "2") (pinfunction "2_2") (pintype "passive"))
      (node (ref "E8/P-2") (pin "2") (pinfunction "2_2") (pintype "passive"))
    )
    (net (code "103") (name "/~{FLAG-ID0}") (class "Default")
      (node (ref "!FLAG-ID0") (pin "1") (pinfunction "1_1") (pintype "passive"))
      (node (ref "E8/10T-2") (pin "14") (pinfunction "14_14") (pintype "passive"))
    )
    (net (code "104") (name "/~{FLAG-ID1}") (class "Default")
      (node (ref "!FLAG-ID1") (pin "1") (pinfunction "1_1") (pintype "passive"))
      (node (ref "E8/10T-2") (pin "10") (pinfunction "10_10") (pintype "passive"))
    )
    (net (code "105") (name "/~{FLAG-OD0}") (class "Default")
      (node (ref "!FLAG-OD0") (pin "1") (pinfunction "1_1") (pintype "passive"))
      (node (ref "E8/10T-2") (pin "6") (pinfunction "6_6") (pintype "passive"))
    )
    (net (code "106") (name "/~{FLAG-OD1}") (class "Default")
      (node (ref "!FLAG-OD1") (pin "1") (pinfunction "1_1") (pintype "passive"))
      (node (ref "E8/10T-2") (pin "2") (pinfunction "2_2") (pintype "passive"))
    )
    (net (code "107") (name "/~{RESET-ID0}") (class "Default")
      (node (ref "!RESET-ID0") (pin "1") (pinfunction "1_1") (pintype "passive"))
      (node (ref "E8/10T-2") (pin "15") (pinfunction "15_15") (pintype "passive"))
    )
    (net (code "108") (name "/~{RESET-ID1}") (class "Default")
      (node (ref "!RESET-ID1") (pin "1") (pinfunction "1_1") (pintype "passive"))
      (node (ref "E8/10T-2") (pin "11") (pinfunction "11_11") (pintype "passive"))
    )
    (net (code "109") (name "/~{RESET-OD0}") (class "Default")
      (node (ref "!RESET-OD0") (pin "1") (pinfunction "1_1") (pintype "passive"))
      (node (ref "E8/10T-2") (pin "7") (pinfunction "7_7") (pintype "passive"))
    )
    (net (code "110") (name "/~{RESET-OD1}") (class "Default")
      (node (ref "!RESET-OD1") (pin "1") (pinfunction "1_1") (pintype "passive"))
      (node (ref "E8/10T-2") (pin "3") (pinfunction "3_3") (pintype "passive"))
    )
    (net (code "111") (name "GND2") (class "Default")
      (node (ref "C10") (pin "2") (pinfunction "2_2") (pintype "passive"))
      (node (ref "C8") (pin "2") (pinfunction "2_2") (pintype "passive"))
      (node (ref "C9") (pin "2") (pinfunction "2_2") (pintype "passive"))
      (node (ref "CGND") (pin "1") (pinfunction "1_1") (pintype "passive"))
      (node (ref "E8/10T") (pin "1") (pinfunction "1_1") (pintype "passive"))
      (node (ref "E8/10T") (pin "16") (pinfunction "16_16") (pintype "passive"))
      (node (ref "E8/A") (pin "1") (pinfunction "1_1") (pintype "passive"))
      (node (ref "E8/A") (pin "16") (pinfunction "16_16") (pintype "passive"))
      (node (ref "E8/D") (pin "1") (pinfunction "1_1") (pintype "passive"))
      (node (ref "E8/D") (pin "32") (pinfunction "32_32") (pintype "passive"))
      (node (ref "E8/M") (pin "1") (pinfunction "1_1") (pintype "passive"))
      (node (ref "E8/M") (pin "32") (pinfunction "32_32") (pintype "passive"))
      (node (ref "E8/P") (pin "1") (pinfunction "1_1") (pintype "passive"))
      (node (ref "E8/P") (pin "32") (pinfunction "32_32") (pintype "passive"))
      (node (ref "E8/T") (pin "1") (pinfunction "1_1") (pintype "passive"))
      (node (ref "E8/T") (pin "32") (pinfunction "32_32") (pintype "passive"))
    )
    (net (code "112") (name "Net-(E8/10T-Pad4)") (class "Default")
      (node (ref "E8/10T") (pin "4") (pinfunction "4_4") (pintype "passive"))
      (node (ref "E8/A") (pin "4") (pinfunction "4_4") (pintype "passive"))
      (node (ref "E8/P") (pin "4") (pinfunction "4_4") (pintype "passive"))
      (node (ref "R63") (pin "1") (pinfunction "1_1") (pintype "passive"))
    )
    (net (code "113") (name "Net-(E8/10T-Pad5)") (class "Default")
      (node (ref "E8/10T") (pin "5") (pinfunction "5_5") (pintype "passive"))
      (node (ref "E8/D") (pin "4") (pinfunction "4_4") (pintype "passive"))
    )
    (net (code "114") (name "Net-(E8/A-Pad5)") (class "Default")
      (node (ref "E8/A") (pin "5") (pinfunction "5_5") (pintype "passive"))
      (node (ref "E8/M") (pin "4") (pinfunction "4_4") (pintype "passive"))
      (node (ref "E8/P") (pin "5") (pinfunction "5_5") (pintype "passive"))
      (node (ref "R64") (pin "1") (pinfunction "1_1") (pintype "passive"))
    )
    (net (code "115") (name "Net-(E8/D-Pad3)") (class "Default")
      (node (ref "E8/D") (pin "3") (pinfunction "3_3") (pintype "passive"))
      (node (ref "E8/T") (pin "3") (pinfunction "3_3") (pintype "passive"))
    )
    (net (code "116") (name "Net-(E8/M-2-Pad1)") (class "Default")
      (node (ref "E8/M-2") (pin "1") (pinfunction "1_1") (pintype "passive"))
      (node (ref "E8/P-2") (pin "1") (pinfunction "1_1") (pintype "passive"))
    )
    (net (code "117") (name "unconnected-(E8/P-2-Pad7)") (class "Default")
      (node (ref "E8/P-2") (pin "7") (pinfunction "7_7") (pintype "passive"))
    )
    (net (code "118") (name "unconnected-(E8/P-2-Pad14)") (class "Default")
      (node (ref "E8/P-2") (pin "14") (pinfunction "14_14") (pintype "passive"))
    )
    (net (code "119") (name "unconnected-(E8/P-2-Pad15)") (class "Default")
      (node (ref "E8/P-2") (pin "15") (pinfunction "15_15") (pintype "passive"))
    )
    (net (code "120") (name "unconnected-(E8/P-2-Pad16)") (class "Default")
      (node (ref "E8/P-2") (pin "16") (pinfunction "16_16") (pintype "passive"))
    )
    (net (code "121") (name "unconnected-(E8/P-Pad29)") (class "Default")
      (node (ref "E8/P") (pin "29") (pinfunction "29_29") (pintype "passive"))
    )
    (net (code "122") (name "unconnected-(E8/T-Pad25)") (class "Default")
      (node (ref "E8/T") (pin "25") (pinfunction "25_25") (pintype "passive"))
    )
    (net (code "123") (name "unconnected-(E8/T-Pad26)") (class "Default")
      (node (ref "E8/T") (pin "26") (pinfunction "26_26") (pintype "passive"))
    )
  )
)
